# LoRa.net
KiCad netlist of a schematic drawn in Altium Designer
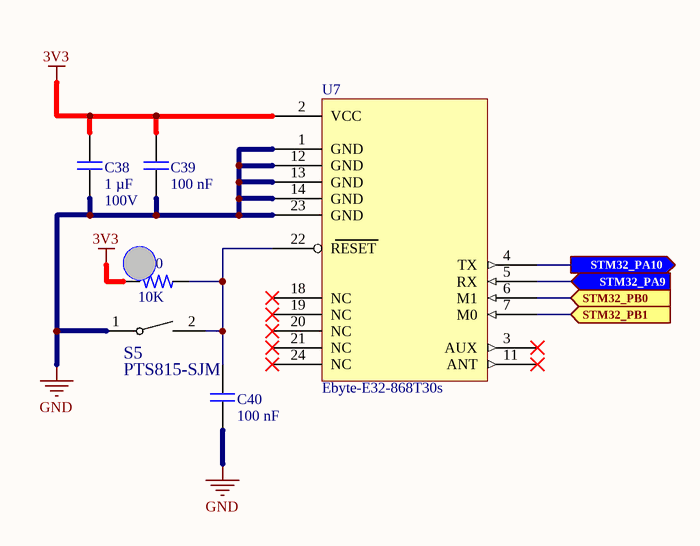
[diagram p0: LoRa.SchDoc]

(export (version "E")
  (design (tool "Eeschema 10.0.6"))
  (components
    (comp (ref "C38")
      (value "1 µF")
      (footprint "MergenElektronik_Capacitors_Ceramics_SMDs_1206_M_NS")
      (description "Mergen Elektronik - Capacitors - Ceramics - SMDs - 1206 - 1 µF - 100V")
      (fields
        (field (name "MANUFACTURER") "Samsung Electro-Mechanics")
        (field (name "TOLERANCE") "±10%")
        (field (name "VOLTAGE RATING") "100V")
      )
      (libsource (lib "MergenElektronik_Capacitors_Ceramics_SMDs") (part "MergenElektronik_Capacitors_Ceramic_SMDs_1µF_100V"))
    )
    (comp (ref "C39")
      (value "100 nF")
      (footprint "MergenElektronik_Capacitors_Ceramics_SMDs_0603_M_NS")
      (description "Mergen Elektronik - Capacitors - Ceramics - SMDs - 0603 - 100 nF - 100V")
      (fields (field (name "MANUFACTURER") "Samsung Electro-Mechanics") (field (name "TOLERANCE") "±10%"))
      (libsource (lib "MergenElektronik_Capacitors_Ceramics_SMDs") (part "MergenElektronik_Capacitors_Ceramic_SMDs_100nF_100V"))
    )
    (comp (ref "C40")
      (value "100 nF")
      (footprint "MergenElektronik_Capacitors_Ceramics_SMDs_0603_M_NS")
      (description "Mergen Elektronik - Capacitors - Ceramics - SMDs - 0603 - 100 nF - 100V")
      (fields (field (name "MANUFACTURER") "Samsung Electro-Mechanics") (field (name "TOLERANCE") "±10%"))
      (libsource (lib "MergenElektronik_Capacitors_Ceramics_SMDs") (part "MergenElektronik_Capacitors_Ceramic_SMDs_100nF_100V"))
    )
    (comp (ref "R30")
      (value "10K")
      (footprint "MergenElektronik_Resistors_ChipResistors_0603_M_NS")
      (description "Mergen Elektronik - Resistors - Chip Resistors - 0603 - 10K")
      (fields (field (name "MANUFACTURER") "Stackpole Electronics Inc") (field (name "POWER") "1/10W"))
      (libsource (lib "MergenElektronik_Resistors_ChipResistors") (part "MergenElektronik_Resistors_ChipResistors_0603_10K"))
    )
    (comp (ref "S5")
      (value "PTS815-SJM")
      (footprint "MergenElektronik_Switches_TactileSwitches_PTS815")
      (description "Mergen Elektronik - Switches - Tactile  Switches")
      (fields (field (name "MANUFACTURER") "C&K"))
      (libsource (lib "MergenElektronik_Switches_TactileSwitches") (part "MergenElektronik_Switches_TactileSwitches_PTS815-SJM"))
    )
    (comp (ref "U7")
      (value "Ebyte-E32-868T30s")
      (footprint "MergenElektronik_Modules_LoRas_Ebyte-E32-xxxxT30x")
      (description "Mergen Elektronik - Modules - LoRas - Ebyte-E32-868T30s")
      (fields (field (name "MANUFACTURER") "Ebyte") (field (name "POWER") "30dBm"))
      (libsource (lib "MergenElektronik_Modules_LoRas") (part "MergenElektronik_Modules_LoRas_Ebyte-E32-868T30s"))
    )
  )
  (nets
    (net (code "1") (name "/STM32_PA9") (class "Default")
      (node (ref "U7") (pin "5") (pinfunction "RX_5") (pintype "input"))
    )
    (net (code "2") (name "/STM32_PA10") (class "Default")
      (node (ref "U7") (pin "4") (pinfunction "TX_4") (pintype "output"))
    )
    (net (code "3") (name "/STM32_PB0") (class "Default")
      (node (ref "U7") (pin "6") (pinfunction "M1_6") (pintype "input"))
    )
    (net (code "4") (name "/STM32_PB1") (class "Default")
      (node (ref "U7") (pin "7") (pinfunction "M0_7") (pintype "input"))
    )
    (net (code "5") (name "3V3") (class "Default")
      (node (ref "C38") (pin "1") (pinfunction "1_1") (pintype "passive"))
      (node (ref "C39") (pin "1") (pinfunction "1_1") (pintype "passive"))
      (node (ref "R30") (pin "1") (pinfunction "1_1") (pintype "passive"))
      (node (ref "U7") (pin "2") (pinfunction "VCC_2") (pintype "power_in"))
    )
    (net (code "6") (name "GND") (class "Default")
      (node (ref "C38") (pin "2") (pinfunction "2_2") (pintype "passive"))
      (node (ref "C39") (pin "2") (pinfunction "2_2") (pintype "passive"))
      (node (ref "C40") (pin "2") (pinfunction "2_2") (pintype "passive"))
      (node (ref "S5") (pin "1") (pinfunction "1_1") (pintype "passive"))
      (node (ref "U7") (pin "1") (pinfunction "GND_1") (pintype "power_in"))
      (node (ref "U7") (pin "12") (pinfunction "GND_12") (pintype "power_in"))
      (node (ref "U7") (pin "13") (pinfunction "GND_13") (pintype "power_in"))
      (node (ref "U7") (pin "14") (pinfunction "GND_14") (pintype "power_in"))
      (node (ref "U7") (pin "23") (pinfunction "GND_23") (pintype "power_in"))
    )
    (net (code "7") (name "Net-(U7-RESET)") (class "Default")
      (node (ref "C40") (pin "1") (pinfunction "1_1") (pintype "passive"))
      (node (ref "R30") (pin "2") (pinfunction "2_2") (pintype "passive"))
      (node (ref "S5") (pin "2") (pinfunction "2_2") (pintype "passive"))
      (node (ref "U7") (pin "22") (pinfunction "RESET_22") (pintype "passive"))
    )
    (net (code "8") (name "unconnected-(U7-ANT-Pad11)") (class "Default")
      (node (ref "U7") (pin "11") (pinfunction "ANT_11") (pintype "output+no_connect"))
    )
    (net (code "9") (name "unconnected-(U7-AUX-Pad3)") (class "Default")
      (node (ref "U7") (pin "3") (pinfunction "AUX_3") (pintype "output+no_connect"))
    )
    (net (code "10") (name "unconnected-(U7-NC-Pad18)") (class "Default")
      (node (ref "U7") (pin "18") (pinfunction "NC_18") (pintype "passive+no_connect"))
    )
    (net (code "11") (name "unconnected-(U7-NC-Pad19)") (class "Default")
      (node (ref "U7") (pin "19") (pinfunction "NC_19") (pintype "passive+no_connect"))
    )
    (net (code "12") (name "unconnected-(U7-NC-Pad20)") (class "Default")
      (node (ref "U7") (pin "20") (pinfunction "NC_20") (pintype "passive+no_connect"))
    )
    (net (code "13") (name "unconnected-(U7-NC-Pad21)") (class "Default")
      (node (ref "U7") (pin "21") (pinfunction "NC_21") (pintype "passive+no_connect"))
    )
    (net (code "14") (name "unconnected-(U7-NC-Pad24)") (class "Default")
      (node (ref "U7") (pin "24") (pinfunction "NC_24") (pintype "passive+no_connect"))
    )
  )
)
